# TRL_v1.net
KiCad netlist of a schematic drawn in EAGLE
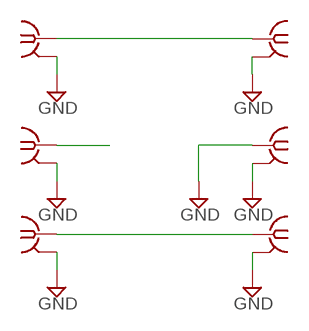
[diagram p0: schematic, sheet 1]

(export (version "E")
  (design (tool "Eeschema 10.0.6"))
  (components
    (comp (ref "X1")
      (value "SMA-142-0711-821/826")
      (footprint "eagle-import:J502-ND-142-0711-821_826")
      (fields (field (name "MF") "JOHNSON COMPONENTS") (field (name "MPN") "142-0711-821"))
      (libsource (lib "eagle-import") (part "SMA-142-0711-821/826"))
    )
    (comp (ref "X2")
      (value "SMA-142-0711-821/826")
      (footprint "eagle-import:J502-ND-142-0711-821_826")
      (fields (field (name "MF") "JOHNSON COMPONENTS") (field (name "MPN") "142-0711-821"))
      (libsource (lib "eagle-import") (part "SMA-142-0711-821/826"))
    )
    (comp (ref "X3")
      (value "SMA-142-0711-821/826")
      (footprint "eagle-import:J502-ND-142-0711-821_826")
      (fields (field (name "MF") "JOHNSON COMPONENTS") (field (name "MPN") "142-0711-821"))
      (libsource (lib "eagle-import") (part "SMA-142-0711-821/826"))
    )
    (comp (ref "X4")
      (value "SMA-142-0711-821/826")
      (footprint "eagle-import:J502-ND-142-0711-821_826")
      (fields (field (name "MF") "JOHNSON COMPONENTS") (field (name "MPN") "142-0711-821"))
      (libsource (lib "eagle-import") (part "SMA-142-0711-821/826"))
    )
    (comp (ref "X5")
      (value "SMA-142-0711-821/826")
      (footprint "eagle-import:J502-ND-142-0711-821_826")
      (fields (field (name "MF") "JOHNSON COMPONENTS") (field (name "MPN") "142-0711-821"))
      (libsource (lib "eagle-import") (part "SMA-142-0711-821/826"))
    )
    (comp (ref "X6")
      (value "SMA-142-0711-821/826")
      (footprint "eagle-import:J502-ND-142-0711-821_826")
      (fields (field (name "MF") "JOHNSON COMPONENTS") (field (name "MPN") "142-0711-821"))
      (libsource (lib "eagle-import") (part "SMA-142-0711-821/826"))
    )
  )
  (nets
    (net (code "1") (name "GND") (class "Default")
      (node (ref "X1") (pin "G@1") (pinfunction "2_G@1") (pintype "passive"))
      (node (ref "X1") (pin "G@2") (pinfunction "2_G@2") (pintype "passive"))
      (node (ref "X1") (pin "G@3") (pinfunction "2_G@3") (pintype "passive"))
      (node (ref "X1") (pin "G@4") (pinfunction "2_G@4") (pintype "passive"))
      (node (ref "X2") (pin "G@1") (pinfunction "2_G@1") (pintype "passive"))
      (node (ref "X2") (pin "G@2") (pinfunction "2_G@2") (pintype "passive"))
      (node (ref "X2") (pin "G@3") (pinfunction "2_G@3") (pintype "passive"))
      (node (ref "X2") (pin "G@4") (pinfunction "2_G@4") (pintype "passive"))
      (node (ref "X3") (pin "G@1") (pinfunction "2_G@1") (pintype "passive"))
      (node (ref "X3") (pin "G@2") (pinfunction "2_G@2") (pintype "passive"))
      (node (ref "X3") (pin "G@3") (pinfunction "2_G@3") (pintype "passive"))
      (node (ref "X3") (pin "G@4") (pinfunction "2_G@4") (pintype "passive"))
      (node (ref "X4") (pin "1") (pinfunction "1_1") (pintype "passive"))
      (node (ref "X4") (pin "G@1") (pinfunction "2_G@1") (pintype "passive"))
      (node (ref "X4") (pin "G@2") (pinfunction "2_G@2") (pintype "passive"))
      (node (ref "X4") (pin "G@3") (pinfunction "2_G@3") (pintype "passive"))
      (node (ref "X4") (pin "G@4") (pinfunction "2_G@4") (pintype "passive"))
      (node (ref "X5") (pin "G@1") (pinfunction "2_G@1") (pintype "passive"))
      (node (ref "X5") (pin "G@2") (pinfunction "2_G@2") (pintype "passive"))
      (node (ref "X5") (pin "G@3") (pinfunction "2_G@3") (pintype "passive"))
      (node (ref "X5") (pin "G@4") (pinfunction "2_G@4") (pintype "passive"))
      (node (ref "X6") (pin "G@1") (pinfunction "2_G@1") (pintype "passive"))
      (node (ref "X6") (pin "G@2") (pinfunction "2_G@2") (pintype "passive"))
      (node (ref "X6") (pin "G@3") (pinfunction "2_G@3") (pintype "passive"))
      (node (ref "X6") (pin "G@4") (pinfunction "2_G@4") (pintype "passive"))
    )
    (net (code "2") (name "Net-(X1-Pad1)") (class "Default")
      (node (ref "X1") (pin "1") (pinfunction "1_1") (pintype "passive"))
      (node (ref "X2") (pin "1") (pinfunction "1_1") (pintype "passive"))
    )
    (net (code "3") (name "Net-(X5-Pad1)") (class "Default")
      (node (ref "X5") (pin "1") (pinfunction "1_1") (pintype "passive"))
      (node (ref "X6") (pin "1") (pinfunction "1_1") (pintype "passive"))
    )
    (net (code "4") (name "unconnected-(X3-Pad1)") (class "Default")
      (node (ref "X3") (pin "1") (pinfunction "1_1") (pintype "passive"))
    )
  )
)
